# npm1300_qeaa_config2.net
KiCad netlist of a schematic drawn in Altium Designer
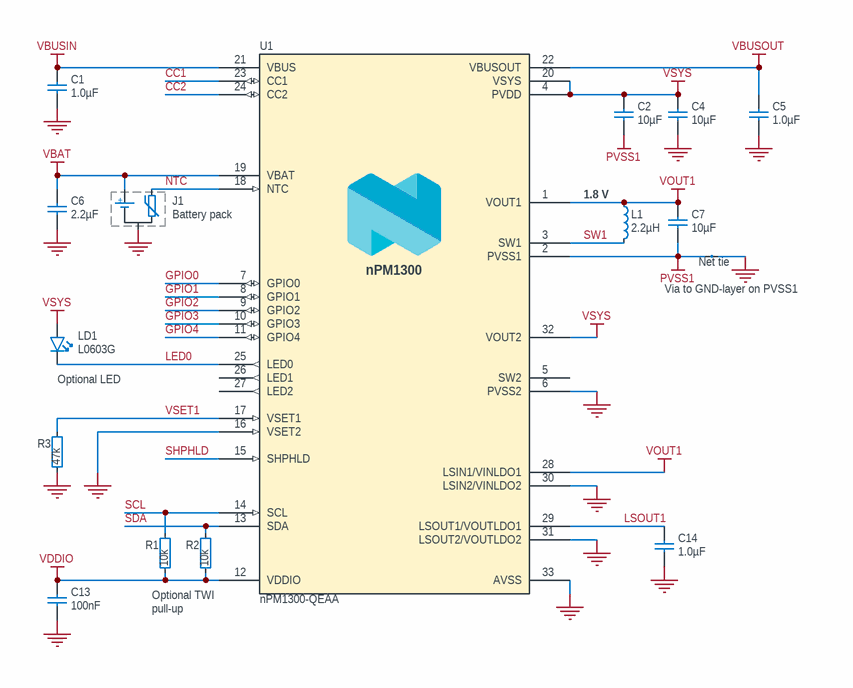
[diagram p0: npm1300_qeaa_config2.SchDoc]

(export (version "E")
  (design (tool "Eeschema 10.0.6"))
  (components
    (comp (ref "C1")
      (value "1.0µF")
      (footprint "CAPC1608X06L")
      (description "Capacitor, Ceramic, 1.0µF 10V X5R 0603,±10%")
      (fields
        (field (name "PART NUMBER") "C0603-1µ0-10V-X5R")
        (field (name "MANUFACTURER") "N.A.")
        (field (name "AUTHOR") "getr")
      )
      (libsource (lib "AltiumLib") (part "CAP"))
    )
    (comp (ref "C2")
      (value "10µF")
      (footprint "CAPC1608X06L")
      (description "Capacitor, Ceramic, X5R, ±20%, 10V")
      (fields
        (field (name "PART NUMBER") "C0603-10µ-10V-X5R")
        (field (name "MANUFACTURER") "N.A.")
        (field (name "AUTHOR") "rubr")
      )
      (libsource (lib "AltiumLib") (part "CAP"))
    )
    (comp (ref "C4")
      (value "10µF")
      (footprint "CAPC1608X06L")
      (description "Capacitor, Ceramic, X5R, ±20%, 10V")
      (fields
        (field (name "PART NUMBER") "C0603-10µ-10V-X5R")
        (field (name "MANUFACTURER") "N.A.")
        (field (name "AUTHOR") "rubr")
      )
      (libsource (lib "AltiumLib") (part "CAP"))
    )
    (comp (ref "C5")
      (value "1.0µF")
      (footprint "CAPC1608X06L")
      (description "Capacitor, Ceramic, 1.0µF 10V X5R 0603,±10%")
      (fields
        (field (name "PART NUMBER") "C0603-1µ0-10V-X5R")
        (field (name "MANUFACTURER") "N.A.")
        (field (name "AUTHOR") "getr")
      )
      (libsource (lib "AltiumLib") (part "CAP"))
    )
    (comp (ref "C6")
      (value "2.2µF")
      (footprint "CAPC1608X06L")
      (description "Capacitor, Ceramic, X5R, ±10%, 25V")
      (fields
        (field (name "PART NUMBER") "C0603-2µ2-25V-X5R-GRM188R61E225KA12D")
        (field (name "MANUFACTURER") "Murata")
        (field (name "AUTHOR") "rsk")
      )
      (libsource (lib "AltiumLib") (part "CAP"))
    )
    (comp (ref "C7")
      (value "10µF")
      (footprint "CAPC1608X06L")
      (description "Capacitor, Ceramic, X5R, ±20%, 10V")
      (fields
        (field (name "PART NUMBER") "C0603-10µ-10V-X5R")
        (field (name "MANUFACTURER") "N.A.")
        (field (name "AUTHOR") "rubr")
      )
      (libsource (lib "AltiumLib") (part "CAP"))
    )
    (comp (ref "C13")
      (value "100nF")
      (footprint "CAPC0603X03L_C")
      (description "Capacitor, Ceramic, X5R, ±10%, 25V")
      (fields
        (field (name "PART NUMBER") "C0201-100n-25V-X5R")
        (field (name "MANUFACTURER") "Murata")
        (field (name "AUTHOR") "rsk")
      )
      (libsource (lib "AltiumLib") (part "CAP"))
    )
    (comp (ref "C14")
      (value "1.0µF")
      (footprint "CAPC1608X06L")
      (description "Capacitor, Ceramic, 1.0µF 10V X5R 0603,±10%")
      (fields
        (field (name "PART NUMBER") "C0603-1µ0-10V-X5R")
        (field (name "MANUFACTURER") "N.A.")
        (field (name "AUTHOR") "getr")
      )
      (libsource (lib "AltiumLib") (part "CAP"))
    )
    (comp (ref "J1")
      (value "Battery pack")
      (footprint "TP_3x1mm_TH")
      (description "Battery pack with NTC")
      (fields
        (field (name "PART NUMBER") "Battery_w/NTC_TP")
        (field (name "MANUFACTURER") "N.A.")
        (field (name "AUTHOR") "rsk")
      )
      (libsource (lib "AltiumLib") (part "Battery_pack_NTC"))
    )
    (comp (ref "L1")
      (value "2.2µH")
      (footprint "INDC2016X10N")
      (description "Inductor, Irms=2.5A, Isat=2.9A, ±20%, DCR=73mΩ")
      (fields
        (field (name "PART NUMBER") "L0806-2µ2-2500mA-73mOhm-CIGT201610EH2R2MNE")
        (field (name "MANUFACTURER") "Samsung Electro-Mechanics America")
        (field (name "AUTHOR") "rsk")
      )
      (libsource (lib "AltiumLib") (part "IND"))
    )
    (comp (ref "LD1")
      (value "L0603G")
      (footprint "LED_0603_G")
      (description "LED 0603 GREEN")
      (fields
        (field (name "PART NUMBER") "150060GS55040")
        (field (name "MANUFACTURER") "Wurth Elektronik")
        (field (name "AUTHOR") "kjp")
      )
      (libsource (lib "AltiumLib") (part "D{colon}LED"))
    )
    (comp (ref "NT1")
      (value "Net tie")
      (footprint "2 PIN STARPOINT")
      (description "Starpoint")
      (fields
        (field (name "PART NUMBER") "2 pin starpoint")
        (field (name "MANUFACTURER") "N.A.")
        (field (name "AUTHOR") "rsk")
      )
      (libsource (lib "AltiumLib") (part "2 pin starpoint"))
    )
    (comp (ref "R1")
      (value "10k")
      (footprint "RESC0603X03L_C")
      (description "Resistor, ±1%, 0.05W")
      (fields
        (field (name "PART NUMBER") "R0201-10k")
        (field (name "MANUFACTURER") "N.A.")
        (field (name "AUTHOR") "rsk")
      )
      (libsource (lib "AltiumLib") (part "RES"))
    )
    (comp (ref "R2")
      (value "10k")
      (footprint "RESC0603X03L_C")
      (description "Resistor, ±1%, 0.05W")
      (fields
        (field (name "PART NUMBER") "R0201-10k")
        (field (name "MANUFACTURER") "N.A.")
        (field (name "AUTHOR") "rsk")
      )
      (libsource (lib "AltiumLib") (part "RES"))
    )
    (comp (ref "R3")
      (value "47k")
      (footprint "RESC0603X03L_C")
      (description "Resistor, ±1%, 0.05W")
      (fields
        (field (name "PART NUMBER") "R0201-47k")
        (field (name "MANUFACTURER") "N.A.")
        (field (name "AUTHOR") "rsk")
      )
      (libsource (lib "AltiumLib") (part "RES"))
    )
    (comp (ref "U1")
      (value "nPM1300-QEAA")
      (footprint "Nordic_QFN50P500X500X90-33N")
      (fields (field (name "MANUFACTURER") "Nordic Semiconductor") (field (name "AUTHOR") "eisk"))
      (libsource (lib "AltiumLib") (part "nPM1300_QEAA"))
    )
  )
  (nets
    (net (code "1") (name "/CC1") (class "Default")
      (node (ref "U1") (pin "23") (pinfunction "CC1_23") (pintype "bidirectional"))
    )
    (net (code "2") (name "/CC2") (class "Default")
      (node (ref "U1") (pin "24") (pinfunction "CC2_24") (pintype "bidirectional"))
    )
    (net (code "3") (name "/GPIO0") (class "Default")
      (node (ref "U1") (pin "7") (pinfunction "GPIO0_7") (pintype "bidirectional"))
    )
    (net (code "4") (name "/GPIO1") (class "Default")
      (node (ref "U1") (pin "8") (pinfunction "GPIO1_8") (pintype "bidirectional"))
    )
    (net (code "5") (name "/GPIO2") (class "Default")
      (node (ref "U1") (pin "9") (pinfunction "GPIO2_9") (pintype "bidirectional"))
    )
    (net (code "6") (name "/GPIO3") (class "Default")
      (node (ref "U1") (pin "10") (pinfunction "GPIO3_10") (pintype "bidirectional"))
    )
    (net (code "7") (name "/GPIO4") (class "Default")
      (node (ref "U1") (pin "11") (pinfunction "GPIO4_11") (pintype "bidirectional"))
    )
    (net (code "8") (name "/LED0") (class "Default")
      (node (ref "LD1") (pin "1") (pinfunction "C_1") (pintype "passive"))
      (node (ref "U1") (pin "25") (pinfunction "LED0_25") (pintype "output"))
    )
    (net (code "9") (name "/LSOUT1") (class "Default")
      (node (ref "C14") (pin "2") (pinfunction "2_2") (pintype "passive"))
      (node (ref "U1") (pin "29") (pinfunction "LSOUT1/VOUTLDO1_29") (pintype "power_in"))
    )
    (net (code "10") (name "/NTC") (class "Default")
      (node (ref "J1") (pin "2") (pinfunction "NTC_2") (pintype "passive"))
      (node (ref "U1") (pin "18") (pinfunction "NTC_18") (pintype "input"))
    )
    (net (code "11") (name "/SCL") (class "Default")
      (node (ref "R1") (pin "1") (pinfunction "1_1") (pintype "passive"))
      (node (ref "U1") (pin "14") (pinfunction "SCL_14") (pintype "input"))
    )
    (net (code "12") (name "/SDA") (class "Default")
      (node (ref "R2") (pin "1") (pinfunction "1_1") (pintype "passive"))
      (node (ref "U1") (pin "13") (pinfunction "SDA_13") (pintype "open_collector"))
    )
    (net (code "13") (name "/SHPHLD") (class "Default")
      (node (ref "U1") (pin "15") (pinfunction "SHPHLD_15") (pintype "input"))
    )
    (net (code "14") (name "/SW1") (class "Default")
      (node (ref "L1") (pin "2") (pinfunction "2_2") (pintype "passive"))
      (node (ref "U1") (pin "3") (pinfunction "SW1_3") (pintype "power_in"))
    )
    (net (code "15") (name "/VSET1") (class "Default")
      (node (ref "R3") (pin "1") (pinfunction "1_1") (pintype "passive"))
      (node (ref "U1") (pin "17") (pinfunction "VSET1_17") (pintype "input"))
    )
    (net (code "16") (name "GND") (class "Default")
      (node (ref "C1") (pin "1") (pinfunction "1_1") (pintype "passive"))
      (node (ref "C13") (pin "2") (pinfunction "2_2") (pintype "passive"))
      (node (ref "C14") (pin "1") (pinfunction "1_1") (pintype "passive"))
      (node (ref "C4") (pin "1") (pinfunction "1_1") (pintype "passive"))
      (node (ref "C5") (pin "1") (pinfunction "1_1") (pintype "passive"))
      (node (ref "C6") (pin "1") (pinfunction "1_1") (pintype "passive"))
      (node (ref "J1") (pin "1") (pinfunction "GND_1") (pintype "passive"))
      (node (ref "NT1") (pin "1") (pintype "passive"))
      (node (ref "R3") (pin "2") (pinfunction "2_2") (pintype "passive"))
      (node (ref "U1") (pin "16") (pinfunction "VSET2_16") (pintype "input"))
      (node (ref "U1") (pin "30") (pinfunction "LSIN2/VINLDO2_30") (pintype "power_in"))
      (node (ref "U1") (pin "31") (pinfunction "LSOUT2/VOUTLDO2_31") (pintype "power_in"))
      (node (ref "U1") (pin "33") (pinfunction "AVSS_33") (pintype "power_in"))
      (node (ref "U1") (pin "6") (pinfunction "PVSS2_6") (pintype "power_in"))
    )
    (net (code "17") (name "PVSS1") (class "Default")
      (node (ref "C2") (pin "1") (pinfunction "1_1") (pintype "passive"))
      (node (ref "C7") (pin "1") (pinfunction "1_1") (pintype "passive"))
      (node (ref "NT1") (pin "2") (pintype "passive"))
      (node (ref "U1") (pin "2") (pinfunction "PVSS1_2") (pintype "power_in"))
    )
    (net (code "18") (name "VBAT") (class "Default")
      (node (ref "C6") (pin "2") (pinfunction "2_2") (pintype "passive"))
      (node (ref "J1") (pin "3") (pinfunction "V+_3") (pintype "passive"))
      (node (ref "U1") (pin "19") (pinfunction "VBAT_19") (pintype "passive"))
    )
    (net (code "19") (name "VBUSIN") (class "Default")
      (node (ref "C1") (pin "2") (pinfunction "2_2") (pintype "passive"))
      (node (ref "U1") (pin "21") (pinfunction "VBUS_21") (pintype "power_in"))
    )
    (net (code "20") (name "VBUSOUT") (class "Default")
      (node (ref "C5") (pin "2") (pinfunction "2_2") (pintype "passive"))
      (node (ref "U1") (pin "22") (pinfunction "VBUSOUT_22") (pintype "power_in"))
    )
    (net (code "21") (name "VDDIO") (class "Default")
      (node (ref "C13") (pin "1") (pinfunction "1_1") (pintype "passive"))
      (node (ref "R1") (pin "2") (pinfunction "2_2") (pintype "passive"))
      (node (ref "R2") (pin "2") (pinfunction "2_2") (pintype "passive"))
      (node (ref "U1") (pin "12") (pinfunction "VDDIO_12") (pintype "power_in"))
    )
    (net (code "22") (name "VOUT1") (class "Default")
      (node (ref "C7") (pin "2") (pinfunction "2_2") (pintype "passive"))
      (node (ref "L1") (pin "1") (pinfunction "1_1") (pintype "passive"))
      (node (ref "U1") (pin "1") (pinfunction "VOUT1_1") (pintype "power_in"))
      (node (ref "U1") (pin "28") (pinfunction "LSIN1/VINLDO1_28") (pintype "power_in"))
    )
    (net (code "23") (name "VSYS") (class "Default")
      (node (ref "C2") (pin "2") (pinfunction "2_2") (pintype "passive"))
      (node (ref "C4") (pin "2") (pinfunction "2_2") (pintype "passive"))
      (node (ref "LD1") (pin "2") (pinfunction "A_2") (pintype "passive"))
      (node (ref "U1") (pin "20") (pinfunction "VSYS_20") (pintype "power_in"))
      (node (ref "U1") (pin "32") (pinfunction "VOUT2_32") (pintype "power_in"))
      (node (ref "U1") (pin "4") (pinfunction "PVDD_4") (pintype "power_in"))
    )
    (net (code "24") (name "unconnected-(U1-LED1-Pad26)") (class "Default")
      (node (ref "U1") (pin "26") (pinfunction "LED1_26") (pintype "output"))
    )
    (net (code "25") (name "unconnected-(U1-LED2-Pad27)") (class "Default")
      (node (ref "U1") (pin "27") (pinfunction "LED2_27") (pintype "output"))
    )
    (net (code "26") (name "unconnected-(U1-SW2-Pad5)") (class "Default")
      (node (ref "U1") (pin "5") (pinfunction "SW2_5") (pintype "power_in"))
    )
  )
)
